# MSP432.net
KiCad netlist of a schematic drawn in Altium Designer
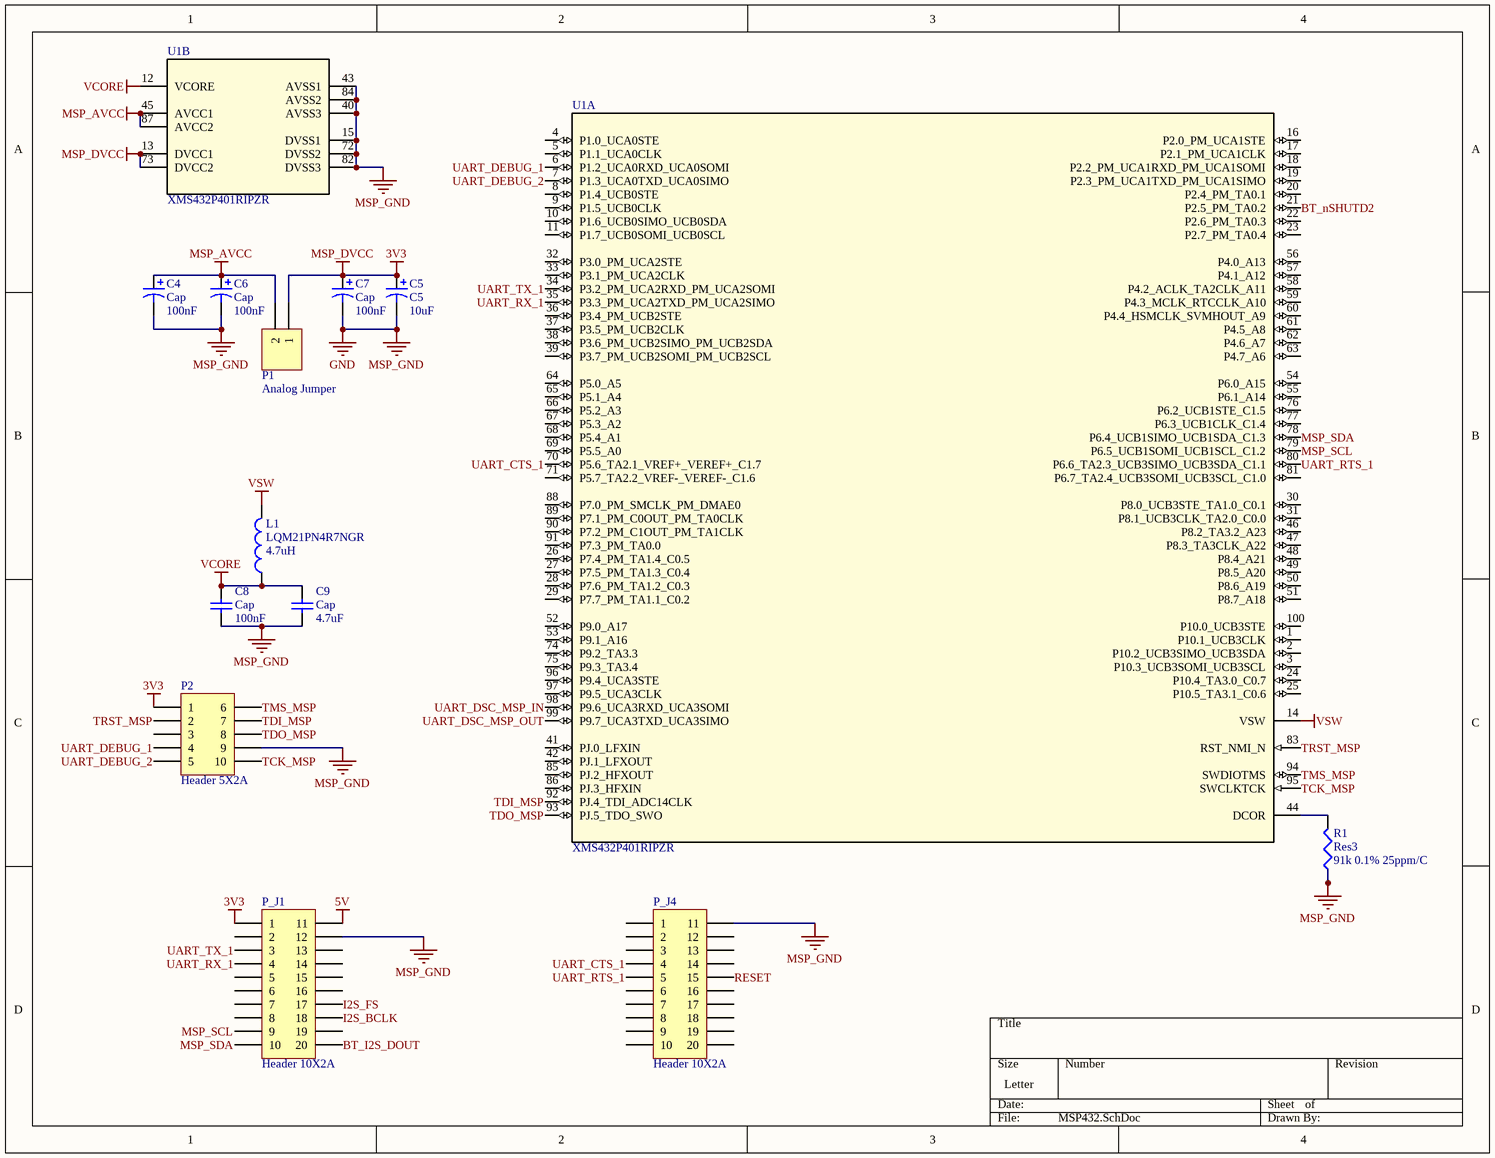
[diagram p0: MSP432.SchDoc]

(export (version "E")
  (design (tool "Eeschema 10.0.6"))
  (components
    (comp (ref "C4")
      (value "Cap")
      (footprint "C0805")
      (description "Polarized Capacitor (Surface Mount)")
      (fields (field (name "ALTIUM_VALUE") "100nF") (field (name "PUBLISHER") "Altium Limited"))
      (libsource (lib "Miscellaneous Devices") (part "Cap Pol3"))
    )
    (comp (ref "C5")
      (value "C5")
      (footprint "C0805")
      (description "Polarized Capacitor (Surface Mount)")
      (fields (field (name "ALTIUM_VALUE") "10uF") (field (name "PUBLISHER") "Altium Limited"))
      (libsource (lib "Miscellaneous Devices") (part "Cap Pol3"))
    )
    (comp (ref "C6")
      (value "Cap")
      (footprint "C0805")
      (description "Polarized Capacitor (Surface Mount)")
      (fields (field (name "ALTIUM_VALUE") "100nF") (field (name "PUBLISHER") "Altium Limited"))
      (libsource (lib "Miscellaneous Devices") (part "Cap Pol3"))
    )
    (comp (ref "C7")
      (value "Cap")
      (footprint "C0805")
      (description "Polarized Capacitor (Surface Mount)")
      (fields (field (name "ALTIUM_VALUE") "100nF") (field (name "PUBLISHER") "Altium Limited"))
      (libsource (lib "Miscellaneous Devices") (part "Cap Pol3"))
    )
    (comp (ref "C8")
      (value "Cap")
      (footprint "C0805")
      (description "Capacitor (Semiconductor SIM Model)")
      (fields (field (name "ALTIUM_VALUE") "100nF") (field (name "PUBLISHER") "Altium Limited"))
      (libsource (lib "Miscellaneous Devices") (part "Cap Semi"))
    )
    (comp (ref "C9")
      (value "Cap")
      (footprint "C0805")
      (description "Capacitor (Semiconductor SIM Model)")
      (fields (field (name "ALTIUM_VALUE") "4.7uF") (field (name "PUBLISHER") "Altium Limited"))
      (libsource (lib "Miscellaneous Devices") (part "Cap Semi"))
    )
    (comp (ref "L1")
      (value "LQM21PN4R7NGR")
      (footprint "6-0805_N")
      (description "Inductor")
      (fields (field (name "ALTIUM_VALUE") "4.7uH") (field (name "PUBLISHER") "Altium Limited"))
      (libsource (lib "Miscellaneous Devices") (part "Inductor"))
    )
    (comp (ref "P1")
      (value "Analog Jumper")
      (footprint "HDR1X2")
      (description "Header, 2-Pin")
      (fields (field (name "PUBLISHER") "Altium Limited"))
      (libsource (lib "Miscellaneous Connectors") (part "Header 2"))
    )
    (comp (ref "P2")
      (value "Header 5X2A")
      (footprint "HDR2X5_CEN")
      (description "Header, 5-Pin, Dual row")
      (fields (field (name "PUBLISHER") "Altium Limited"))
      (libsource (lib "Miscellaneous Connectors") (part "Header 5X2A"))
    )
    (comp (ref "P_J1")
      (value "Header 10X2A")
      (footprint "HDR2X10_CEN")
      (description "Header, 10-Pin, Dual row")
      (fields (field (name "PUBLISHER") "Altium Limited"))
      (libsource (lib "Miscellaneous Connectors") (part "Header 10X2A"))
    )
    (comp (ref "P_J4")
      (value "Header 10X2A")
      (footprint "HDR2X10_CEN")
      (description "Header, 10-Pin, Dual row")
      (fields (field (name "PUBLISHER") "Altium Limited"))
      (libsource (lib "Miscellaneous Connectors") (part "Header 10X2A"))
    )
    (comp (ref "R1")
      (value "Res3")
      (footprint "14-1210")
      (description "Resistor")
      (fields (field (name "ALTIUM_VALUE") "91k 0.1% 25ppm/C") (field (name "PUBLISHER") "Altium Limited"))
      (libsource (lib "Miscellaneous Devices") (part "Res3"))
    )
    (comp (ref "U1")
      (value "XMS432P401RIPZR")
      (footprint "PZ0100A_N")
      (description "Imported")
      (fields (field (name "MANUFACTURER") "Texas Instruments"))
      (libsource (lib "XMS432P401R") (part "XMS432P401RIPZR"))
    )
  )
  (nets
    (net (code "1") (name "/BT_I2S_DOUT") (class "Default")
      (node (ref "P_J1") (pin "20") (pinfunction "20_20") (pintype "passive"))
    )
    (net (code "2") (name "/BT_nSHUTD2") (class "Default")
      (node (ref "U1") (pin "21") (pinfunction "P2.5_PM_TA0.2_21") (pintype "bidirectional"))
    )
    (net (code "3") (name "/I2S_BCLK") (class "Default")
      (node (ref "P_J1") (pin "18") (pinfunction "18_18") (pintype "passive"))
    )
    (net (code "4") (name "/I2S_FS") (class "Default")
      (node (ref "P_J1") (pin "17") (pinfunction "17_17") (pintype "passive"))
    )
    (net (code "5") (name "/MSP_SCL") (class "Default")
      (node (ref "P_J1") (pin "9") (pinfunction "9_9") (pintype "passive"))
      (node (ref "U1") (pin "79") (pinfunction "P6.5_UCB1SOMI_UCB1SCL_C1.2_79") (pintype "bidirectional"))
    )
    (net (code "6") (name "/MSP_SDA") (class "Default")
      (node (ref "P_J1") (pin "10") (pinfunction "10_10") (pintype "passive"))
      (node (ref "U1") (pin "78") (pinfunction "P6.4_UCB1SIMO_UCB1SDA_C1.3_78") (pintype "bidirectional"))
    )
    (net (code "7") (name "/RESET") (class "Default")
      (node (ref "P_J4") (pin "15") (pinfunction "15_15") (pintype "passive"))
    )
    (net (code "8") (name "/TCK_MSP") (class "Default")
      (node (ref "P2") (pin "10") (pinfunction "10_10") (pintype "passive"))
      (node (ref "U1") (pin "95") (pinfunction "SWCLKTCK_95") (pintype "input"))
    )
    (net (code "9") (name "/TDI_MSP") (class "Default")
      (node (ref "P2") (pin "7") (pinfunction "7_7") (pintype "passive"))
      (node (ref "U1") (pin "92") (pinfunction "PJ.4_TDI_ADC14CLK_92") (pintype "bidirectional"))
    )
    (net (code "10") (name "/TDO_MSP") (class "Default")
      (node (ref "P2") (pin "8") (pinfunction "8_8") (pintype "passive"))
      (node (ref "U1") (pin "93") (pinfunction "PJ.5_TDO_SWO_93") (pintype "bidirectional"))
    )
    (net (code "11") (name "/TMS_MSP") (class "Default")
      (node (ref "P2") (pin "6") (pinfunction "6_6") (pintype "passive"))
      (node (ref "U1") (pin "94") (pinfunction "SWDIOTMS_94") (pintype "bidirectional"))
    )
    (net (code "12") (name "/TRST_MSP") (class "Default")
      (node (ref "P2") (pin "2") (pinfunction "2_2") (pintype "passive"))
      (node (ref "U1") (pin "83") (pinfunction "RST_NMI_N_83") (pintype "input"))
    )
    (net (code "13") (name "/UART_CTS_1") (class "Default")
      (node (ref "P_J4") (pin "4") (pinfunction "4_4") (pintype "passive"))
      (node (ref "U1") (pin "70") (pinfunction "P5.6_TA2.1_VREF+_VEREF+_C1.7_70") (pintype "bidirectional"))
    )
    (net (code "14") (name "/UART_DEBUG_1") (class "Default")
      (node (ref "P2") (pin "4") (pinfunction "4_4") (pintype "passive"))
      (node (ref "U1") (pin "6") (pinfunction "P1.2_UCA0RXD_UCA0SOMI_6") (pintype "bidirectional"))
    )
    (net (code "15") (name "/UART_DEBUG_2") (class "Default")
      (node (ref "P2") (pin "5") (pinfunction "5_5") (pintype "passive"))
      (node (ref "U1") (pin "7") (pinfunction "P1.3_UCA0TXD_UCA0SIMO_7") (pintype "bidirectional"))
    )
    (net (code "16") (name "/UART_DSC_MSP_IN") (class "Default")
      (node (ref "U1") (pin "98") (pinfunction "P9.6_UCA3RXD_UCA3SOMI_98") (pintype "bidirectional"))
    )
    (net (code "17") (name "/UART_DSC_MSP_OUT") (class "Default")
      (node (ref "U1") (pin "99") (pinfunction "P9.7_UCA3TXD_UCA3SIMO_99") (pintype "bidirectional"))
    )
    (net (code "18") (name "/UART_RTS_1") (class "Default")
      (node (ref "P_J4") (pin "5") (pinfunction "5_5") (pintype "passive"))
      (node (ref "U1") (pin "80") (pinfunction "P6.6_TA2.3_UCB3SIMO_UCB3SDA_C1.1_80") (pintype "bidirectional"))
    )
    (net (code "19") (name "/UART_RX_1") (class "Default")
      (node (ref "P_J1") (pin "4") (pinfunction "4_4") (pintype "passive"))
      (node (ref "U1") (pin "35") (pinfunction "P3.3_PM_UCA2TXD_PM_UCA2SIMO_35") (pintype "bidirectional"))
    )
    (net (code "20") (name "/UART_TX_1") (class "Default")
      (node (ref "P_J1") (pin "3") (pinfunction "3_3") (pintype "passive"))
      (node (ref "U1") (pin "34") (pinfunction "P3.2_PM_UCA2RXD_PM_UCA2SOMI_34") (pintype "bidirectional"))
    )
    (net (code "21") (name "3V3") (class "Default")
      (node (ref "C5") (pin "1") (pinfunction "1_1") (pintype "passive"))
      (node (ref "C7") (pin "1") (pinfunction "1_1") (pintype "passive"))
      (node (ref "P1") (pin "1") (pinfunction "1_1") (pintype "passive"))
      (node (ref "P2") (pin "1") (pinfunction "1_1") (pintype "passive"))
      (node (ref "P_J1") (pin "1") (pinfunction "1_1") (pintype "passive"))
      (node (ref "U1") (pin "13") (pinfunction "DVCC1_13") (pintype "power_in"))
      (node (ref "U1") (pin "73") (pinfunction "DVCC2_73") (pintype "power_in"))
    )
    (net (code "22") (name "5V") (class "Default")
      (node (ref "P_J1") (pin "11") (pinfunction "11_11") (pintype "passive"))
    )
    (net (code "23") (name "GND") (class "Default")
      (node (ref "C4") (pin "2") (pinfunction "2_2") (pintype "passive"))
      (node (ref "C5") (pin "2") (pinfunction "2_2") (pintype "passive"))
      (node (ref "C6") (pin "2") (pinfunction "2_2") (pintype "passive"))
      (node (ref "C7") (pin "2") (pinfunction "2_2") (pintype "passive"))
      (node (ref "C8") (pin "1") (pinfunction "1_1") (pintype "passive"))
      (node (ref "C9") (pin "2") (pinfunction "2_2") (pintype "passive"))
      (node (ref "P2") (pin "9") (pinfunction "9_9") (pintype "passive"))
      (node (ref "P_J1") (pin "12") (pinfunction "12_12") (pintype "passive"))
      (node (ref "P_J4") (pin "11") (pinfunction "11_11") (pintype "passive"))
      (node (ref "R1") (pin "1") (pinfunction "1_1") (pintype "passive"))
      (node (ref "U1") (pin "15") (pinfunction "DVSS1_15") (pintype "power_in"))
      (node (ref "U1") (pin "40") (pinfunction "AVSS3_40") (pintype "power_in"))
      (node (ref "U1") (pin "43") (pinfunction "AVSS1_43") (pintype "power_in"))
      (node (ref "U1") (pin "72") (pinfunction "DVSS2_72") (pintype "power_in"))
      (node (ref "U1") (pin "82") (pinfunction "DVSS3_82") (pintype "power_in"))
      (node (ref "U1") (pin "84") (pinfunction "AVSS2_84") (pintype "power_in"))
    )
    (net (code "24") (name "MSP_AVCC") (class "Default")
      (node (ref "C4") (pin "1") (pinfunction "1_1") (pintype "passive"))
      (node (ref "C6") (pin "1") (pinfunction "1_1") (pintype "passive"))
      (node (ref "P1") (pin "2") (pinfunction "2_2") (pintype "passive"))
      (node (ref "U1") (pin "45") (pinfunction "AVCC1_45") (pintype "power_in"))
      (node (ref "U1") (pin "87") (pinfunction "AVCC2_87") (pintype "power_in"))
    )
    (net (code "25") (name "Net-(U1A-DCOR)") (class "Default")
      (node (ref "R1") (pin "2") (pinfunction "2_2") (pintype "passive"))
      (node (ref "U1") (pin "44") (pinfunction "DCOR_44") (pintype "passive"))
    )
    (net (code "26") (name "VCORE") (class "Default")
      (node (ref "C8") (pin "2") (pinfunction "2_2") (pintype "passive"))
      (node (ref "C9") (pin "1") (pinfunction "1_1") (pintype "passive"))
      (node (ref "L1") (pin "1") (pinfunction "1_1") (pintype "passive"))
      (node (ref "U1") (pin "12") (pinfunction "VCORE_12") (pintype "power_in"))
    )
    (net (code "27") (name "VSW") (class "Default")
      (node (ref "L1") (pin "2") (pinfunction "2_2") (pintype "passive"))
      (node (ref "U1") (pin "14") (pinfunction "VSW_14") (pintype "passive"))
    )
    (net (code "28") (name "unconnected-(P2-Pad3)") (class "Default")
      (node (ref "P2") (pin "3") (pinfunction "3_3") (pintype "passive"))
    )
    (net (code "29") (name "unconnected-(P_J1-Pad2)") (class "Default")
      (node (ref "P_J1") (pin "2") (pinfunction "2_2") (pintype "passive"))
    )
    (net (code "30") (name "unconnected-(P_J1-Pad5)") (class "Default")
      (node (ref "P_J1") (pin "5") (pinfunction "5_5") (pintype "passive"))
    )
    (net (code "31") (name "unconnected-(P_J1-Pad6)") (class "Default")
      (node (ref "P_J1") (pin "6") (pinfunction "6_6") (pintype "passive"))
    )
    (net (code "32") (name "unconnected-(P_J1-Pad7)") (class "Default")
      (node (ref "P_J1") (pin "7") (pinfunction "7_7") (pintype "passive"))
    )
    (net (code "33") (name "unconnected-(P_J1-Pad8)") (class "Default")
      (node (ref "P_J1") (pin "8") (pinfunction "8_8") (pintype "passive"))
    )
    (net (code "34") (name "unconnected-(P_J1-Pad13)") (class "Default")
      (node (ref "P_J1") (pin "13") (pinfunction "13_13") (pintype "passive"))
    )
    (net (code "35") (name "unconnected-(P_J1-Pad14)") (class "Default")
      (node (ref "P_J1") (pin "14") (pinfunction "14_14") (pintype "passive"))
    )
    (net (code "36") (name "unconnected-(P_J1-Pad15)") (class "Default")
      (node (ref "P_J1") (pin "15") (pinfunction "15_15") (pintype "passive"))
    )
    (net (code "37") (name "unconnected-(P_J1-Pad16)") (class "Default")
      (node (ref "P_J1") (pin "16") (pinfunction "16_16") (pintype "passive"))
    )
    (net (code "38") (name "unconnected-(P_J1-Pad19)") (class "Default")
      (node (ref "P_J1") (pin "19") (pinfunction "19_19") (pintype "passive"))
    )
    (net (code "39") (name "unconnected-(P_J4-Pad1)") (class "Default")
      (node (ref "P_J4") (pin "1") (pinfunction "1_1") (pintype "passive"))
    )
    (net (code "40") (name "unconnected-(P_J4-Pad2)") (class "Default")
      (node (ref "P_J4") (pin "2") (pinfunction "2_2") (pintype "passive"))
    )
    (net (code "41") (name "unconnected-(P_J4-Pad3)") (class "Default")
      (node (ref "P_J4") (pin "3") (pinfunction "3_3") (pintype "passive"))
    )
    (net (code "42") (name "unconnected-(P_J4-Pad6)") (class "Default")
      (node (ref "P_J4") (pin "6") (pinfunction "6_6") (pintype "passive"))
    )
    (net (code "43") (name "unconnected-(P_J4-Pad7)") (class "Default")
      (node (ref "P_J4") (pin "7") (pinfunction "7_7") (pintype "passive"))
    )
    (net (code "44") (name "unconnected-(P_J4-Pad8)") (class "Default")
      (node (ref "P_J4") (pin "8") (pinfunction "8_8") (pintype "passive"))
    )
    (net (code "45") (name "unconnected-(P_J4-Pad9)") (class "Default")
      (node (ref "P_J4") (pin "9") (pinfunction "9_9") (pintype "passive"))
    )
    (net (code "46") (name "unconnected-(P_J4-Pad10)") (class "Default")
      (node (ref "P_J4") (pin "10") (pinfunction "10_10") (pintype "passive"))
    )
    (net (code "47") (name "unconnected-(P_J4-Pad12)") (class "Default")
      (node (ref "P_J4") (pin "12") (pinfunction "12_12") (pintype "passive"))
    )
    (net (code "48") (name "unconnected-(P_J4-Pad13)") (class "Default")
      (node (ref "P_J4") (pin "13") (pinfunction "13_13") (pintype "passive"))
    )
    (net (code "49") (name "unconnected-(P_J4-Pad14)") (class "Default")
      (node (ref "P_J4") (pin "14") (pinfunction "14_14") (pintype "passive"))
    )
    (net (code "50") (name "unconnected-(P_J4-Pad16)") (class "Default")
      (node (ref "P_J4") (pin "16") (pinfunction "16_16") (pintype "passive"))
    )
    (net (code "51") (name "unconnected-(P_J4-Pad17)") (class "Default")
      (node (ref "P_J4") (pin "17") (pinfunction "17_17") (pintype "passive"))
    )
    (net (code "52") (name "unconnected-(P_J4-Pad18)") (class "Default")
      (node (ref "P_J4") (pin "18") (pinfunction "18_18") (pintype "passive"))
    )
    (net (code "53") (name "unconnected-(P_J4-Pad19)") (class "Default")
      (node (ref "P_J4") (pin "19") (pinfunction "19_19") (pintype "passive"))
    )
    (net (code "54") (name "unconnected-(P_J4-Pad20)") (class "Default")
      (node (ref "P_J4") (pin "20") (pinfunction "20_20") (pintype "passive"))
    )
    (net (code "55") (name "unconnected-(U1A-P1.0_UCA0STE-Pad4)") (class "Default")
      (node (ref "U1") (pin "4") (pinfunction "P1.0_UCA0STE_4") (pintype "bidirectional"))
    )
    (net (code "56") (name "unconnected-(U1A-P1.1_UCA0CLK-Pad5)") (class "Default")
      (node (ref "U1") (pin "5") (pinfunction "P1.1_UCA0CLK_5") (pintype "bidirectional"))
    )
    (net (code "57") (name "unconnected-(U1A-P1.4_UCB0STE-Pad8)") (class "Default")
      (node (ref "U1") (pin "8") (pinfunction "P1.4_UCB0STE_8") (pintype "bidirectional"))
    )
    (net (code "58") (name "unconnected-(U1A-P1.5_UCB0CLK-Pad9)") (class "Default")
      (node (ref "U1") (pin "9") (pinfunction "P1.5_UCB0CLK_9") (pintype "bidirectional"))
    )
    (net (code "59") (name "unconnected-(U1A-P1.6_UCB0SIMO_UCB0SDA-Pad10)") (class "Default")
      (node (ref "U1") (pin "10") (pinfunction "P1.6_UCB0SIMO_UCB0SDA_10") (pintype "bidirectional"))
    )
    (net (code "60") (name "unconnected-(U1A-P1.7_UCB0SOMI_UCB0SCL-Pad11)") (class "Default")
      (node (ref "U1") (pin "11") (pinfunction "P1.7_UCB0SOMI_UCB0SCL_11") (pintype "bidirectional"))
    )
    (net (code "61") (name "unconnected-(U1A-P2.0_PM_UCA1STE-Pad16)") (class "Default")
      (node (ref "U1") (pin "16") (pinfunction "P2.0_PM_UCA1STE_16") (pintype "bidirectional"))
    )
    (net (code "62") (name "unconnected-(U1A-P2.1_PM_UCA1CLK-Pad17)") (class "Default")
      (node (ref "U1") (pin "17") (pinfunction "P2.1_PM_UCA1CLK_17") (pintype "bidirectional"))
    )
    (net (code "63") (name "unconnected-(U1A-P2.2_PM_UCA1RXD_PM_UCA1SOMI-Pad18)") (class "Default")
      (node (ref "U1") (pin "18") (pinfunction "P2.2_PM_UCA1RXD_PM_UCA1SOMI_18") (pintype "bidirectional"))
    )
    (net (code "64") (name "unconnected-(U1A-P2.3_PM_UCA1TXD_PM_UCA1SIMO-Pad19)") (class "Default")
      (node (ref "U1") (pin "19") (pinfunction "P2.3_PM_UCA1TXD_PM_UCA1SIMO_19") (pintype "bidirectional"))
    )
    (net (code "65") (name "unconnected-(U1A-P2.4_PM_TA0.1-Pad20)") (class "Default")
      (node (ref "U1") (pin "20") (pinfunction "P2.4_PM_TA0.1_20") (pintype "bidirectional"))
    )
    (net (code "66") (name "unconnected-(U1A-P2.6_PM_TA0.3-Pad22)") (class "Default")
      (node (ref "U1") (pin "22") (pinfunction "P2.6_PM_TA0.3_22") (pintype "bidirectional"))
    )
    (net (code "67") (name "unconnected-(U1A-P2.7_PM_TA0.4-Pad23)") (class "Default")
      (node (ref "U1") (pin "23") (pinfunction "P2.7_PM_TA0.4_23") (pintype "bidirectional"))
    )
    (net (code "68") (name "unconnected-(U1A-P3.0_PM_UCA2STE-Pad32)") (class "Default")
      (node (ref "U1") (pin "32") (pinfunction "P3.0_PM_UCA2STE_32") (pintype "bidirectional"))
    )
    (net (code "69") (name "unconnected-(U1A-P3.1_PM_UCA2CLK-Pad33)") (class "Default")
      (node (ref "U1") (pin "33") (pinfunction "P3.1_PM_UCA2CLK_33") (pintype "bidirectional"))
    )
    (net (code "70") (name "unconnected-(U1A-P3.4_PM_UCB2STE-Pad36)") (class "Default")
      (node (ref "U1") (pin "36") (pinfunction "P3.4_PM_UCB2STE_36") (pintype "bidirectional"))
    )
    (net (code "71") (name "unconnected-(U1A-P3.5_PM_UCB2CLK-Pad37)") (class "Default")
      (node (ref "U1") (pin "37") (pinfunction "P3.5_PM_UCB2CLK_37") (pintype "bidirectional"))
    )
    (net (code "72") (name "unconnected-(U1A-P3.6_PM_UCB2SIMO_PM_UCB2SDA-Pad38)") (class "Default")
      (node (ref "U1") (pin "38") (pinfunction "P3.6_PM_UCB2SIMO_PM_UCB2SDA_38") (pintype "bidirectional"))
    )
    (net (code "73") (name "unconnected-(U1A-P3.7_PM_UCB2SOMI_PM_UCB2SCL-Pad39)") (class "Default")
      (node (ref "U1") (pin "39") (pinfunction "P3.7_PM_UCB2SOMI_PM_UCB2SCL_39") (pintype "bidirectional"))
    )
    (net (code "74") (name "unconnected-(U1A-P4.0_A13-Pad56)") (class "Default")
      (node (ref "U1") (pin "56") (pinfunction "P4.0_A13_56") (pintype "bidirectional"))
    )
    (net (code "75") (name "unconnected-(U1A-P4.1_A12-Pad57)") (class "Default")
      (node (ref "U1") (pin "57") (pinfunction "P4.1_A12_57") (pintype "bidirectional"))
    )
    (net (code "76") (name "unconnected-(U1A-P4.2_ACLK_TA2CLK_A11-Pad58)") (class "Default")
      (node (ref "U1") (pin "58") (pinfunction "P4.2_ACLK_TA2CLK_A11_58") (pintype "bidirectional"))
    )
    (net (code "77") (name "unconnected-(U1A-P4.3_MCLK_RTCCLK_A10-Pad59)") (class "Default")
      (node (ref "U1") (pin "59") (pinfunction "P4.3_MCLK_RTCCLK_A10_59") (pintype "bidirectional"))
    )
    (net (code "78") (name "unconnected-(U1A-P4.4_HSMCLK_SVMHOUT_A9-Pad60)") (class "Default")
      (node (ref "U1") (pin "60") (pinfunction "P4.4_HSMCLK_SVMHOUT_A9_60") (pintype "bidirectional"))
    )
    (net (code "79") (name "unconnected-(U1A-P4.5_A8-Pad61)") (class "Default")
      (node (ref "U1") (pin "61") (pinfunction "P4.5_A8_61") (pintype "bidirectional"))
    )
    (net (code "80") (name "unconnected-(U1A-P4.6_A7-Pad62)") (class "Default")
      (node (ref "U1") (pin "62") (pinfunction "P4.6_A7_62") (pintype "bidirectional"))
    )
    (net (code "81") (name "unconnected-(U1A-P4.7_A6-Pad63)") (class "Default")
      (node (ref "U1") (pin "63") (pinfunction "P4.7_A6_63") (pintype "bidirectional"))
    )
    (net (code "82") (name "unconnected-(U1A-P5.0_A5-Pad64)") (class "Default")
      (node (ref "U1") (pin "64") (pinfunction "P5.0_A5_64") (pintype "bidirectional"))
    )
    (net (code "83") (name "unconnected-(U1A-P5.1_A4-Pad65)") (class "Default")
      (node (ref "U1") (pin "65") (pinfunction "P5.1_A4_65") (pintype "bidirectional"))
    )
    (net (code "84") (name "unconnected-(U1A-P5.2_A3-Pad66)") (class "Default")
      (node (ref "U1") (pin "66") (pinfunction "P5.2_A3_66") (pintype "bidirectional"))
    )
    (net (code "85") (name "unconnected-(U1A-P5.3_A2-Pad67)") (class "Default")
      (node (ref "U1") (pin "67") (pinfunction "P5.3_A2_67") (pintype "bidirectional"))
    )
    (net (code "86") (name "unconnected-(U1A-P5.4_A1-Pad68)") (class "Default")
      (node (ref "U1") (pin "68") (pinfunction "P5.4_A1_68") (pintype "bidirectional"))
    )
    (net (code "87") (name "unconnected-(U1A-P5.5_A0-Pad69)") (class "Default")
      (node (ref "U1") (pin "69") (pinfunction "P5.5_A0_69") (pintype "bidirectional"))
    )
    (net (code "88") (name "unconnected-(U1A-P5.7_TA2.2_VREF-_VEREF-_C1.6-Pad71)") (class "Default")
      (node (ref "U1") (pin "71") (pinfunction "P5.7_TA2.2_VREF-_VEREF-_C1.6_71") (pintype "bidirectional"))
    )
    (net (code "89") (name "unconnected-(U1A-P6.0_A15-Pad54)") (class "Default")
      (node (ref "U1") (pin "54") (pinfunction "P6.0_A15_54") (pintype "bidirectional"))
    )
    (net (code "90") (name "unconnected-(U1A-P6.1_A14-Pad55)") (class "Default")
      (node (ref "U1") (pin "55") (pinfunction "P6.1_A14_55") (pintype "bidirectional"))
    )
    (net (code "91") (name "unconnected-(U1A-P6.2_UCB1STE_C1.5-Pad76)") (class "Default")
      (node (ref "U1") (pin "76") (pinfunction "P6.2_UCB1STE_C1.5_76") (pintype "bidirectional"))
    )
    (net (code "92") (name "unconnected-(U1A-P6.3_UCB1CLK_C1.4-Pad77)") (class "Default")
      (node (ref "U1") (pin "77") (pinfunction "P6.3_UCB1CLK_C1.4_77") (pintype "bidirectional"))
    )
    (net (code "93") (name "unconnected-(U1A-P6.7_TA2.4_UCB3SOMI_UCB3SCL_C1.0-Pad81)") (class "Default")
      (node (ref "U1") (pin "81") (pinfunction "P6.7_TA2.4_UCB3SOMI_UCB3SCL_C1.0_81") (pintype "bidirectional"))
    )
    (net (code "94") (name "unconnected-(U1A-P7.0_PM_SMCLK_PM_DMAE0-Pad88)") (class "Default")
      (node (ref "U1") (pin "88") (pinfunction "P7.0_PM_SMCLK_PM_DMAE0_88") (pintype "bidirectional"))
    )
    (net (code "95") (name "unconnected-(U1A-P7.1_PM_C0OUT_PM_TA0CLK-Pad89)") (class "Default")
      (node (ref "U1") (pin "89") (pinfunction "P7.1_PM_C0OUT_PM_TA0CLK_89") (pintype "bidirectional"))
    )
    (net (code "96") (name "unconnected-(U1A-P7.2_PM_C1OUT_PM_TA1CLK-Pad90)") (class "Default")
      (node (ref "U1") (pin "90") (pinfunction "P7.2_PM_C1OUT_PM_TA1CLK_90") (pintype "bidirectional"))
    )
    (net (code "97") (name "unconnected-(U1A-P7.3_PM_TA0.0-Pad91)") (class "Default")
      (node (ref "U1") (pin "91") (pinfunction "P7.3_PM_TA0.0_91") (pintype "bidirectional"))
    )
    (net (code "98") (name "unconnected-(U1A-P7.4_PM_TA1.4_C0.5-Pad26)") (class "Default")
      (node (ref "U1") (pin "26") (pinfunction "P7.4_PM_TA1.4_C0.5_26") (pintype "bidirectional"))
    )
    (net (code "99") (name "unconnected-(U1A-P7.5_PM_TA1.3_C0.4-Pad27)") (class "Default")
      (node (ref "U1") (pin "27") (pinfunction "P7.5_PM_TA1.3_C0.4_27") (pintype "bidirectional"))
    )
    (net (code "100") (name "unconnected-(U1A-P7.6_PM_TA1.2_C0.3-Pad28)") (class "Default")
      (node (ref "U1") (pin "28") (pinfunction "P7.6_PM_TA1.2_C0.3_28") (pintype "bidirectional"))
    )
    (net (code "101") (name "unconnected-(U1A-P7.7_PM_TA1.1_C0.2-Pad29)") (class "Default")
      (node (ref "U1") (pin "29") (pinfunction "P7.7_PM_TA1.1_C0.2_29") (pintype "bidirectional"))
    )
    (net (code "102") (name "unconnected-(U1A-P8.0_UCB3STE_TA1.0_C0.1-Pad30)") (class "Default")
      (node (ref "U1") (pin "30") (pinfunction "P8.0_UCB3STE_TA1.0_C0.1_30") (pintype "bidirectional"))
    )
    (net (code "103") (name "unconnected-(U1A-P8.1_UCB3CLK_TA2.0_C0.0-Pad31)") (class "Default")
      (node (ref "U1") (pin "31") (pinfunction "P8.1_UCB3CLK_TA2.0_C0.0_31") (pintype "bidirectional"))
    )
    (net (code "104") (name "unconnected-(U1A-P8.2_TA3.2_A23-Pad46)") (class "Default")
      (node (ref "U1") (pin "46") (pinfunction "P8.2_TA3.2_A23_46") (pintype "bidirectional"))
    )
    (net (code "105") (name "unconnected-(U1A-P8.3_TA3CLK_A22-Pad47)") (class "Default")
      (node (ref "U1") (pin "47") (pinfunction "P8.3_TA3CLK_A22_47") (pintype "bidirectional"))
    )
    (net (code "106") (name "unconnected-(U1A-P8.4_A21-Pad48)") (class "Default")
      (node (ref "U1") (pin "48") (pinfunction "P8.4_A21_48") (pintype "bidirectional"))
    )
    (net (code "107") (name "unconnected-(U1A-P8.5_A20-Pad49)") (class "Default")
      (node (ref "U1") (pin "49") (pinfunction "P8.5_A20_49") (pintype "bidirectional"))
    )
    (net (code "108") (name "unconnected-(U1A-P8.6_A19-Pad50)") (class "Default")
      (node (ref "U1") (pin "50") (pinfunction "P8.6_A19_50") (pintype "bidirectional"))
    )
    (net (code "109") (name "unconnected-(U1A-P8.7_A18-Pad51)") (class "Default")
      (node (ref "U1") (pin "51") (pinfunction "P8.7_A18_51") (pintype "bidirectional"))
    )
    (net (code "110") (name "unconnected-(U1A-P9.0_A17-Pad52)") (class "Default")
      (node (ref "U1") (pin "52") (pinfunction "P9.0_A17_52") (pintype "bidirectional"))
    )
    (net (code "111") (name "unconnected-(U1A-P9.1_A16-Pad53)") (class "Default")
      (node (ref "U1") (pin "53") (pinfunction "P9.1_A16_53") (pintype "bidirectional"))
    )
    (net (code "112") (name "unconnected-(U1A-P9.2_TA3.3-Pad74)") (class "Default")
      (node (ref "U1") (pin "74") (pinfunction "P9.2_TA3.3_74") (pintype "bidirectional"))
    )
    (net (code "113") (name "unconnected-(U1A-P9.3_TA3.4-Pad75)") (class "Default")
      (node (ref "U1") (pin "75") (pinfunction "P9.3_TA3.4_75") (pintype "bidirectional"))
    )
    (net (code "114") (name "unconnected-(U1A-P9.4_UCA3STE-Pad96)") (class "Default")
      (node (ref "U1") (pin "96") (pinfunction "P9.4_UCA3STE_96") (pintype "bidirectional"))
    )
    (net (code "115") (name "unconnected-(U1A-P9.5_UCA3CLK-Pad97)") (class "Default")
      (node (ref "U1") (pin "97") (pinfunction "P9.5_UCA3CLK_97") (pintype "bidirectional"))
    )
    (net (code "116") (name "unconnected-(U1A-P10.0_UCB3STE-Pad100)") (class "Default")
      (node (ref "U1") (pin "100") (pinfunction "P10.0_UCB3STE_100") (pintype "bidirectional"))
    )
    (net (code "117") (name "unconnected-(U1A-P10.1_UCB3CLK-Pad1)") (class "Default")
      (node (ref "U1") (pin "1") (pinfunction "P10.1_UCB3CLK_1") (pintype "bidirectional"))
    )
    (net (code "118") (name "unconnected-(U1A-P10.2_UCB3SIMO_UCB3SDA-Pad2)") (class "Default")
      (node (ref "U1") (pin "2") (pinfunction "P10.2_UCB3SIMO_UCB3SDA_2") (pintype "bidirectional"))
    )
    (net (code "119") (name "unconnected-(U1A-P10.3_UCB3SOMI_UCB3SCL-Pad3)") (class "Default")
      (node (ref "U1") (pin "3") (pinfunction "P10.3_UCB3SOMI_UCB3SCL_3") (pintype "bidirectional"))
    )
    (net (code "120") (name "unconnected-(U1A-P10.4_TA3.0_C0.7-Pad24)") (class "Default")
      (node (ref "U1") (pin "24") (pinfunction "P10.4_TA3.0_C0.7_24") (pintype "bidirectional"))
    )
    (net (code "121") (name "unconnected-(U1A-P10.5_TA3.1_C0.6-Pad25)") (class "Default")
      (node (ref "U1") (pin "25") (pinfunction "P10.5_TA3.1_C0.6_25") (pintype "bidirectional"))
    )
    (net (code "122") (name "unconnected-(U1A-PJ.0_LFXIN-Pad41)") (class "Default")
      (node (ref "U1") (pin "41") (pinfunction "PJ.0_LFXIN_41") (pintype "bidirectional"))
    )
    (net (code "123") (name "unconnected-(U1A-PJ.1_LFXOUT-Pad42)") (class "Default")
      (node (ref "U1") (pin "42") (pinfunction "PJ.1_LFXOUT_42") (pintype "bidirectional"))
    )
    (net (code "124") (name "unconnected-(U1A-PJ.2_HFXOUT-Pad85)") (class "Default")
      (node (ref "U1") (pin "85") (pinfunction "PJ.2_HFXOUT_85") (pintype "bidirectional"))
    )
    (net (code "125") (name "unconnected-(U1A-PJ.3_HFXIN-Pad86)") (class "Default")
      (node (ref "U1") (pin "86") (pinfunction "PJ.3_HFXIN_86") (pintype "bidirectional"))
    )
  )
)
